# battery5_2.net
KiCad netlist of a schematic drawn in EAGLE
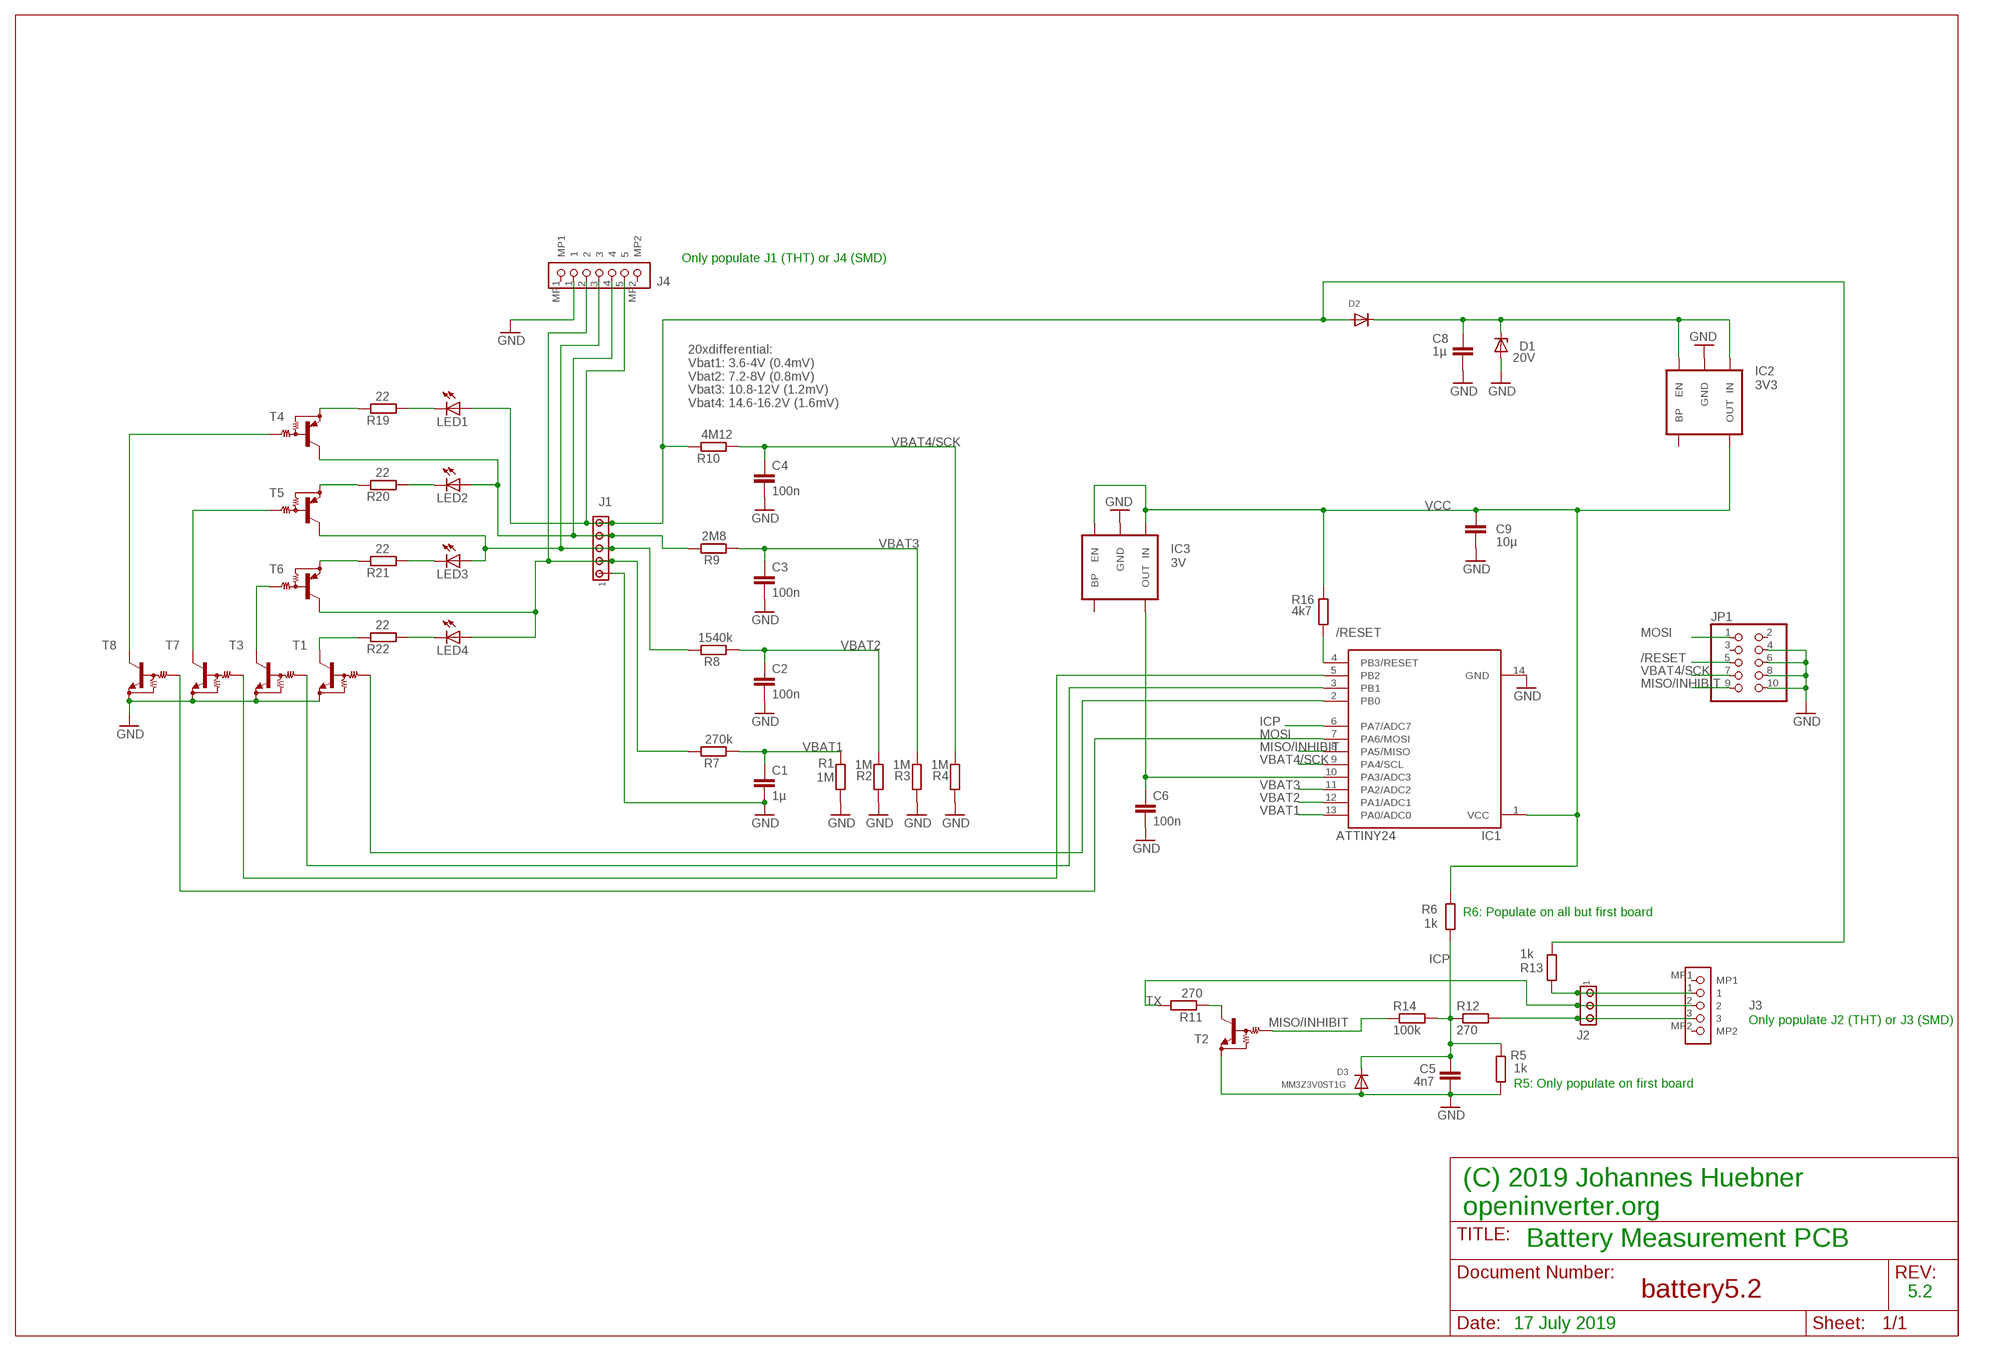
[diagram p0: schematic, sheet 1]

(export (version "E")
  (design (tool "Eeschema 10.0.6"))
  (components
    (comp (ref "C1")
      (value "1µ")
      (footprint "eagle-import:C0603")
      (libsource (lib "eagle-import") (part "C-EUC0603"))
    )
    (comp (ref "C2")
      (value "100n")
      (footprint "eagle-import:C0603")
      (libsource (lib "eagle-import") (part "C-EUC0603"))
    )
    (comp (ref "C3")
      (value "100n")
      (footprint "eagle-import:C0603")
      (libsource (lib "eagle-import") (part "C-EUC0603"))
    )
    (comp (ref "C4")
      (value "100n")
      (footprint "eagle-import:C0603")
      (libsource (lib "eagle-import") (part "C-EUC0603"))
    )
    (comp (ref "C5")
      (value "4n7")
      (footprint "eagle-import:C0603")
      (libsource (lib "eagle-import") (part "C-EUC0603"))
    )
    (comp (ref "C6")
      (value "100n")
      (footprint "eagle-import:C0603")
      (libsource (lib "eagle-import") (part "C-EUC0603"))
    )
    (comp (ref "C8")
      (value "1µ")
      (footprint "eagle-import:C0805")
      (libsource (lib "eagle-import") (part "C-EUC0805"))
    )
    (comp (ref "C9")
      (value "10µ")
      (footprint "eagle-import:C0805")
      (libsource (lib "eagle-import") (part "C-EUC0805"))
    )
    (comp (ref "D1")
      (value "20V")
      (footprint "eagle-import:SMB")
      (libsource (lib "eagle-import") (part "ZENER-DIODESMB"))
    )
    (comp (ref "D2")
      (value "DIODESOD-323F")
      (footprint "eagle-import:SOD-323F")
      (libsource (lib "eagle-import") (part "DIODESOD-323F"))
    )
    (comp (ref "D3")
      (value "MM3Z3V0ST1G")
      (footprint "eagle-import:SOD-323F")
      (libsource (lib "eagle-import") (part "DIODESOD-323F"))
    )
    (comp (ref "IC1")
      (value "ATTINY24")
      (footprint "eagle-import:SO014")
      (libsource (lib "eagle-import") (part "ATTINY24"))
    )
    (comp (ref "IC2")
      (value "3V3")
      (footprint "eagle-import:SOT23-5")
      (libsource (lib "eagle-import") (part "V_REG_LDOSMD"))
    )
    (comp (ref "IC3")
      (value "3V")
      (footprint "eagle-import:SOT23-5")
      (libsource (lib "eagle-import") (part "V_REG_LDOSMD"))
    )
    (comp (ref "J1")
      (value "MTA05-100")
      (footprint "eagle-import:10X05MTA")
      (libsource (lib "eagle-import") (part "MTA05-100"))
    )
    (comp (ref "J2")
      (value "MTA03-100")
      (footprint "eagle-import:10X03MTA")
      (libsource (lib "eagle-import") (part "MTA03-100"))
    )
    (comp (ref "J3")
      (value "BM03B-PASS-1-TFT_(LF)(SN)")
      (footprint "eagle-import:BM03BPASS1TFTLFSN")
      (fields (field (name "MANUFACTURER_PART_NUMBER") "BM03B-PASS-1-TFT (LF)(SN)"))
      (libsource (lib "eagle-import") (part "BM03B-PASS-1-TFT_(LF)(SN)"))
    )
    (comp (ref "J4")
      (value "BM05B-PASS-1-TFT_(LF)(SN)SMD")
      (footprint "eagle-import:BM05BPASS1TFTLFSN")
      (libsource (lib "eagle-import") (part "BM05B-PASS-1-TFT_(LF)(SN)SMD"))
    )
    (comp (ref "JP1")
      (value "PINHD-2X5")
      (footprint "eagle-import:2X05")
      (libsource (lib "eagle-import") (part "PINHD-2X5"))
    )
    (comp (ref "LED1")
      (value "150060GS75000")
      (footprint "eagle-import:CHIPLED_0805")
      (libsource (lib "eagle-import") (part "LEDCHIPLED_0805"))
    )
    (comp (ref "LED2")
      (value "150060GS75000")
      (footprint "eagle-import:CHIPLED_0805")
      (libsource (lib "eagle-import") (part "LEDCHIPLED_0805"))
    )
    (comp (ref "LED3")
      (value "150060GS75000")
      (footprint "eagle-import:CHIPLED_0805")
      (libsource (lib "eagle-import") (part "LEDCHIPLED_0805"))
    )
    (comp (ref "LED4")
      (value "150060GS75000")
      (footprint "eagle-import:CHIPLED_0805")
      (libsource (lib "eagle-import") (part "LEDCHIPLED_0805"))
    )
    (comp (ref "R1")
      (value "1M")
      (footprint "eagle-import:R0603")
      (libsource (lib "eagle-import") (part "R-EU_R0603"))
    )
    (comp (ref "R2")
      (value "1M")
      (footprint "eagle-import:R0603")
      (libsource (lib "eagle-import") (part "R-EU_R0603"))
    )
    (comp (ref "R3")
      (value "1M")
      (footprint "eagle-import:R0603")
      (libsource (lib "eagle-import") (part "R-EU_R0603"))
    )
    (comp (ref "R4")
      (value "1M")
      (footprint "eagle-import:R0603")
      (libsource (lib "eagle-import") (part "R-EU_R0603"))
    )
    (comp (ref "R5")
      (value "1k")
      (footprint "eagle-import:R0603")
      (libsource (lib "eagle-import") (part "R-EU_R0603"))
    )
    (comp (ref "R6")
      (value "1k")
      (footprint "eagle-import:R0603")
      (libsource (lib "eagle-import") (part "R-EU_R0603"))
    )
    (comp (ref "R7")
      (value "270k")
      (footprint "eagle-import:R0603")
      (libsource (lib "eagle-import") (part "R-EU_R0603"))
    )
    (comp (ref "R8")
      (value "1540k")
      (footprint "eagle-import:R0603")
      (libsource (lib "eagle-import") (part "R-EU_R0603"))
    )
    (comp (ref "R9")
      (value "2M8")
      (footprint "eagle-import:R0603")
      (libsource (lib "eagle-import") (part "R-EU_R0603"))
    )
    (comp (ref "R10")
      (value "4M12")
      (footprint "eagle-import:R0603")
      (libsource (lib "eagle-import") (part "R-EU_R0603"))
    )
    (comp (ref "R11")
      (value "270")
      (footprint "eagle-import:R0603")
      (libsource (lib "eagle-import") (part "R-EU_R0603"))
    )
    (comp (ref "R12")
      (value "270")
      (footprint "eagle-import:R0603")
      (libsource (lib "eagle-import") (part "R-EU_R0603"))
    )
    (comp (ref "R13")
      (value "1k")
      (footprint "eagle-import:R0603")
      (libsource (lib "eagle-import") (part "R-EU_R0603"))
    )
    (comp (ref "R14")
      (value "100k")
      (footprint "eagle-import:R0603")
      (libsource (lib "eagle-import") (part "R-EU_R0603"))
    )
    (comp (ref "R16")
      (value "4k7")
      (footprint "eagle-import:R0603")
      (libsource (lib "eagle-import") (part "R-EU_R0603"))
    )
    (comp (ref "R19")
      (value "22")
      (footprint "eagle-import:R0805")
      (libsource (lib "eagle-import") (part "R-EU_R0805"))
    )
    (comp (ref "R20")
      (value "22")
      (footprint "eagle-import:R0805")
      (libsource (lib "eagle-import") (part "R-EU_R0805"))
    )
    (comp (ref "R21")
      (value "22")
      (footprint "eagle-import:R0805")
      (libsource (lib "eagle-import") (part "R-EU_R0805"))
    )
    (comp (ref "R22")
      (value "22")
      (footprint "eagle-import:R0805")
      (libsource (lib "eagle-import") (part "R-EU_R0805"))
    )
    (comp (ref "T1")
      (value "MMUN2233")
      (footprint "eagle-import:SC59-BEC")
      (libsource (lib "eagle-import") (part "-NPN_DRIVER-SC59-BECMUN2211T1"))
    )
    (comp (ref "T2")
      (value "MMUN2233")
      (footprint "eagle-import:SC59-BEC")
      (libsource (lib "eagle-import") (part "-NPN_DRIVER-SC59-BECMUN2211T1"))
    )
    (comp (ref "T3")
      (value "MMUN2233")
      (footprint "eagle-import:SC59-BEC")
      (libsource (lib "eagle-import") (part "-NPN_DRIVER-SC59-BECMUN2211T1"))
    )
    (comp (ref "T4")
      (value "MMUN2111LT1G")
      (footprint "eagle-import:SC59-BEC")
      (libsource (lib "eagle-import") (part "-PNP_DRIVER-SC59-BECMUN2111T1"))
    )
    (comp (ref "T5")
      (value "MMUN2111LT1G")
      (footprint "eagle-import:SC59-BEC")
      (libsource (lib "eagle-import") (part "-PNP_DRIVER-SC59-BECMUN2111T1"))
    )
    (comp (ref "T6")
      (value "MMUN2111LT1G")
      (footprint "eagle-import:SC59-BEC")
      (libsource (lib "eagle-import") (part "-PNP_DRIVER-SC59-BECMUN2111T1"))
    )
    (comp (ref "T7")
      (value "MMUN2233")
      (footprint "eagle-import:SC59-BEC")
      (libsource (lib "eagle-import") (part "-NPN_DRIVER-SC59-BECMUN2211T1"))
    )
    (comp (ref "T8")
      (value "MMUN2233")
      (footprint "eagle-import:SC59-BEC")
      (libsource (lib "eagle-import") (part "-NPN_DRIVER-SC59-BECMUN2211T1"))
    )
  )
  (nets
    (net (code "1") (name "/ICP") (class "Default")
      (node (ref "C5") (pin "1") (pinfunction "1_1") (pintype "passive"))
      (node (ref "D3") (pin "C") (pinfunction "C_C") (pintype "passive"))
      (node (ref "IC1") (pin "6") (pinfunction "PA7/ADC7_6") (pintype "bidirectional"))
      (node (ref "R12") (pin "1") (pinfunction "1_1") (pintype "passive"))
      (node (ref "R14") (pin "2") (pinfunction "2_2") (pintype "passive"))
      (node (ref "R5") (pin "2") (pinfunction "2_2") (pintype "passive"))
      (node (ref "R6") (pin "1") (pinfunction "1_1") (pintype "passive"))
    )
    (net (code "2") (name "/MISO{slash}INHIBIT") (class "Default")
      (node (ref "IC1") (pin "8") (pinfunction "PA5/MISO_8") (pintype "bidirectional"))
      (node (ref "JP1") (pin "9") (pinfunction "9_9") (pintype "passive"))
      (node (ref "R14") (pin "1") (pinfunction "1_1") (pintype "passive"))
      (node (ref "T2") (pin "B") (pinfunction "B_B") (pintype "passive"))
    )
    (net (code "3") (name "/MOSI") (class "Default")
      (node (ref "IC1") (pin "7") (pinfunction "PA6/MOSI_7") (pintype "bidirectional"))
      (node (ref "JP1") (pin "1") (pinfunction "1_1") (pintype "passive"))
      (node (ref "T8") (pin "B") (pinfunction "B_B") (pintype "passive"))
    )
    (net (code "4") (name "/TX") (class "Default")
      (node (ref "J2") (pin "2") (pinfunction "2_2") (pintype "passive"))
      (node (ref "J3") (pin "2") (pinfunction "2_2") (pintype "bidirectional"))
      (node (ref "R11") (pin "2") (pinfunction "2_2") (pintype "passive"))
    )
    (net (code "5") (name "/VBAT1") (class "Default")
      (node (ref "C1") (pin "1") (pinfunction "1_1") (pintype "passive"))
      (node (ref "IC1") (pin "13") (pinfunction "PA0/ADC0_13") (pintype "bidirectional"))
      (node (ref "R1") (pin "1") (pinfunction "1_1") (pintype "passive"))
      (node (ref "R7") (pin "1") (pinfunction "1_1") (pintype "passive"))
    )
    (net (code "6") (name "/VBAT2") (class "Default")
      (node (ref "C2") (pin "1") (pinfunction "1_1") (pintype "passive"))
      (node (ref "IC1") (pin "12") (pinfunction "PA1/ADC1_12") (pintype "bidirectional"))
      (node (ref "R2") (pin "1") (pinfunction "1_1") (pintype "passive"))
      (node (ref "R8") (pin "1") (pinfunction "1_1") (pintype "passive"))
    )
    (net (code "7") (name "/VBAT3") (class "Default")
      (node (ref "C3") (pin "1") (pinfunction "1_1") (pintype "passive"))
      (node (ref "IC1") (pin "11") (pinfunction "PA2/ADC2_11") (pintype "bidirectional"))
      (node (ref "R3") (pin "1") (pinfunction "1_1") (pintype "passive"))
      (node (ref "R9") (pin "1") (pinfunction "1_1") (pintype "passive"))
    )
    (net (code "8") (name "/VBAT4{slash}SCK") (class "Default")
      (node (ref "C4") (pin "1") (pinfunction "1_1") (pintype "passive"))
      (node (ref "IC1") (pin "9") (pinfunction "PA4/SCL_9") (pintype "bidirectional"))
      (node (ref "JP1") (pin "7") (pinfunction "7_7") (pintype "passive"))
      (node (ref "R10") (pin "1") (pinfunction "1_1") (pintype "passive"))
      (node (ref "R4") (pin "1") (pinfunction "1_1") (pintype "passive"))
    )
    (net (code "9") (name "/VCC") (class "Default")
      (node (ref "C9") (pin "1") (pinfunction "1_1") (pintype "passive"))
      (node (ref "IC1") (pin "1") (pinfunction "VCC_1") (pintype "bidirectional"))
      (node (ref "IC2") (pin "5") (pinfunction "OUT_5") (pintype "passive"))
      (node (ref "IC3") (pin "1") (pinfunction "IN_1") (pintype "input"))
      (node (ref "IC3") (pin "3") (pinfunction "EN_3") (pintype "input"))
      (node (ref "R16") (pin "1") (pinfunction "1_1") (pintype "passive"))
      (node (ref "R6") (pin "2") (pinfunction "2_2") (pintype "passive"))
    )
    (net (code "10") (name "/{slash}RESET") (class "Default")
      (node (ref "IC1") (pin "4") (pinfunction "PB3/RESET_4") (pintype "bidirectional"))
      (node (ref "JP1") (pin "5") (pinfunction "5_5") (pintype "passive"))
      (node (ref "R16") (pin "2") (pinfunction "2_2") (pintype "passive"))
    )
    (net (code "11") (name "GND") (class "Default")
      (node (ref "C1") (pin "2") (pinfunction "2_2") (pintype "passive"))
      (node (ref "C2") (pin "2") (pinfunction "2_2") (pintype "passive"))
      (node (ref "C3") (pin "2") (pinfunction "2_2") (pintype "passive"))
      (node (ref "C4") (pin "2") (pinfunction "2_2") (pintype "passive"))
      (node (ref "C5") (pin "2") (pinfunction "2_2") (pintype "passive"))
      (node (ref "C6") (pin "2") (pinfunction "2_2") (pintype "passive"))
      (node (ref "C8") (pin "2") (pinfunction "2_2") (pintype "passive"))
      (node (ref "C9") (pin "2") (pinfunction "2_2") (pintype "passive"))
      (node (ref "D1") (pin "A") (pinfunction "A_A") (pintype "passive"))
      (node (ref "D3") (pin "A") (pinfunction "A_A") (pintype "passive"))
      (node (ref "IC1") (pin "14") (pinfunction "GND_14") (pintype "bidirectional"))
      (node (ref "IC2") (pin "2") (pinfunction "GND_2") (pintype "input"))
      (node (ref "IC3") (pin "2") (pinfunction "GND_2") (pintype "input"))
      (node (ref "J1") (pin "1") (pinfunction "1_1") (pintype "passive"))
      (node (ref "J4") (pin "1") (pinfunction "1_1") (pintype "bidirectional"))
      (node (ref "JP1") (pin "10") (pinfunction "10_10") (pintype "passive"))
      (node (ref "JP1") (pin "4") (pinfunction "4_4") (pintype "passive"))
      (node (ref "JP1") (pin "6") (pinfunction "6_6") (pintype "passive"))
      (node (ref "JP1") (pin "8") (pinfunction "8_8") (pintype "passive"))
      (node (ref "R1") (pin "2") (pinfunction "2_2") (pintype "passive"))
      (node (ref "R2") (pin "2") (pinfunction "2_2") (pintype "passive"))
      (node (ref "R3") (pin "2") (pinfunction "2_2") (pintype "passive"))
      (node (ref "R4") (pin "2") (pinfunction "2_2") (pintype "passive"))
      (node (ref "R5") (pin "1") (pinfunction "1_1") (pintype "passive"))
      (node (ref "T1") (pin "E") (pinfunction "E_E") (pintype "passive"))
      (node (ref "T2") (pin "E") (pinfunction "E_E") (pintype "passive"))
      (node (ref "T3") (pin "E") (pinfunction "E_E") (pintype "passive"))
      (node (ref "T7") (pin "E") (pinfunction "E_E") (pintype "passive"))
      (node (ref "T8") (pin "E") (pinfunction "E_E") (pintype "passive"))
    )
    (net (code "12") (name "Net-(D2-PadA)") (class "Default")
      (node (ref "D2") (pin "A") (pinfunction "A_A") (pintype "passive"))
      (node (ref "J1") (pin "5") (pinfunction "5_5") (pintype "passive"))
      (node (ref "J4") (pin "5") (pinfunction "5_5") (pintype "bidirectional"))
      (node (ref "LED1") (pin "A") (pinfunction "A_A") (pintype "passive"))
      (node (ref "R10") (pin "2") (pinfunction "2_2") (pintype "passive"))
      (node (ref "R13") (pin "1") (pinfunction "1_1") (pintype "passive"))
    )
    (net (code "13") (name "Net-(IC1-PA3{slash}ADC3)") (class "Default")
      (node (ref "C6") (pin "1") (pinfunction "1_1") (pintype "passive"))
      (node (ref "IC1") (pin "10") (pinfunction "PA3/ADC3_10") (pintype "bidirectional"))
      (node (ref "IC3") (pin "5") (pinfunction "OUT_5") (pintype "passive"))
    )
    (net (code "14") (name "Net-(IC1-PB0)") (class "Default")
      (node (ref "IC1") (pin "2") (pinfunction "PB0_2") (pintype "bidirectional"))
      (node (ref "T1") (pin "B") (pinfunction "B_B") (pintype "passive"))
    )
    (net (code "15") (name "Net-(IC1-PB1)") (class "Default")
      (node (ref "IC1") (pin "3") (pinfunction "PB1_3") (pintype "bidirectional"))
      (node (ref "T3") (pin "B") (pinfunction "B_B") (pintype "passive"))
    )
    (net (code "16") (name "Net-(IC1-PB2)") (class "Default")
      (node (ref "IC1") (pin "5") (pinfunction "PB2_5") (pintype "bidirectional"))
      (node (ref "T7") (pin "B") (pinfunction "B_B") (pintype "passive"))
    )
    (net (code "17") (name "Net-(IC2-EN)") (class "Default")
      (node (ref "C8") (pin "1") (pinfunction "1_1") (pintype "passive"))
      (node (ref "D1") (pin "C") (pinfunction "C_C") (pintype "passive"))
      (node (ref "D2") (pin "C") (pinfunction "C_C") (pintype "passive"))
      (node (ref "IC2") (pin "1") (pinfunction "IN_1") (pintype "input"))
      (node (ref "IC2") (pin "3") (pinfunction "EN_3") (pintype "input"))
    )
    (net (code "18") (name "Net-(J1-Pad2)") (class "Default")
      (node (ref "J1") (pin "2") (pinfunction "2_2") (pintype "passive"))
      (node (ref "J4") (pin "2") (pinfunction "2_2") (pintype "bidirectional"))
      (node (ref "LED4") (pin "A") (pinfunction "A_A") (pintype "passive"))
      (node (ref "R7") (pin "2") (pinfunction "2_2") (pintype "passive"))
      (node (ref "T6") (pin "C") (pinfunction "C_C") (pintype "passive"))
    )
    (net (code "19") (name "Net-(J1-Pad3)") (class "Default")
      (node (ref "J1") (pin "3") (pinfunction "3_3") (pintype "passive"))
      (node (ref "J4") (pin "3") (pinfunction "3_3") (pintype "bidirectional"))
      (node (ref "LED3") (pin "A") (pinfunction "A_A") (pintype "passive"))
      (node (ref "R8") (pin "2") (pinfunction "2_2") (pintype "passive"))
      (node (ref "T5") (pin "C") (pinfunction "C_C") (pintype "passive"))
    )
    (net (code "20") (name "Net-(J1-Pad4)") (class "Default")
      (node (ref "J1") (pin "4") (pinfunction "4_4") (pintype "passive"))
      (node (ref "J4") (pin "4") (pinfunction "4_4") (pintype "bidirectional"))
      (node (ref "LED2") (pin "A") (pinfunction "A_A") (pintype "passive"))
      (node (ref "R9") (pin "2") (pinfunction "2_2") (pintype "passive"))
      (node (ref "T4") (pin "C") (pinfunction "C_C") (pintype "passive"))
    )
    (net (code "21") (name "Net-(J2-Pad1)") (class "Default")
      (node (ref "J2") (pin "1") (pinfunction "1_1") (pintype "passive"))
      (node (ref "J3") (pin "1") (pinfunction "1_1") (pintype "bidirectional"))
      (node (ref "R13") (pin "2") (pinfunction "2_2") (pintype "passive"))
    )
    (net (code "22") (name "Net-(J2-Pad3)") (class "Default")
      (node (ref "J2") (pin "3") (pinfunction "3_3") (pintype "passive"))
      (node (ref "J3") (pin "3") (pinfunction "3_3") (pintype "bidirectional"))
      (node (ref "R12") (pin "2") (pinfunction "2_2") (pintype "passive"))
    )
    (net (code "23") (name "Net-(LED1-PadC)") (class "Default")
      (node (ref "LED1") (pin "C") (pinfunction "C_C") (pintype "passive"))
      (node (ref "R19") (pin "1") (pinfunction "1_1") (pintype "passive"))
    )
    (net (code "24") (name "Net-(LED2-PadC)") (class "Default")
      (node (ref "LED2") (pin "C") (pinfunction "C_C") (pintype "passive"))
      (node (ref "R20") (pin "1") (pinfunction "1_1") (pintype "passive"))
    )
    (net (code "25") (name "Net-(LED3-PadC)") (class "Default")
      (node (ref "LED3") (pin "C") (pinfunction "C_C") (pintype "passive"))
      (node (ref "R21") (pin "1") (pinfunction "1_1") (pintype "passive"))
    )
    (net (code "26") (name "Net-(LED4-PadC)") (class "Default")
      (node (ref "LED4") (pin "C") (pinfunction "C_C") (pintype "passive"))
      (node (ref "R22") (pin "1") (pinfunction "1_1") (pintype "passive"))
    )
    (net (code "27") (name "Net-(R11-Pad1)") (class "Default")
      (node (ref "R11") (pin "1") (pinfunction "1_1") (pintype "passive"))
      (node (ref "T2") (pin "C") (pinfunction "C_C") (pintype "passive"))
    )
    (net (code "28") (name "Net-(R19-Pad2)") (class "Default")
      (node (ref "R19") (pin "2") (pinfunction "2_2") (pintype "passive"))
      (node (ref "T4") (pin "E") (pinfunction "E_E") (pintype "passive"))
    )
    (net (code "29") (name "Net-(R20-Pad2)") (class "Default")
      (node (ref "R20") (pin "2") (pinfunction "2_2") (pintype "passive"))
      (node (ref "T5") (pin "E") (pinfunction "E_E") (pintype "passive"))
    )
    (net (code "30") (name "Net-(R21-Pad2)") (class "Default")
      (node (ref "R21") (pin "2") (pinfunction "2_2") (pintype "passive"))
      (node (ref "T6") (pin "E") (pinfunction "E_E") (pintype "passive"))
    )
    (net (code "31") (name "Net-(R22-Pad2)") (class "Default")
      (node (ref "R22") (pin "2") (pinfunction "2_2") (pintype "passive"))
      (node (ref "T1") (pin "C") (pinfunction "C_C") (pintype "passive"))
    )
    (net (code "32") (name "Net-(T3-PadC)") (class "Default")
      (node (ref "T3") (pin "C") (pinfunction "C_C") (pintype "passive"))
      (node (ref "T6") (pin "B") (pinfunction "B_B") (pintype "passive"))
    )
    (net (code "33") (name "Net-(T4-PadB)") (class "Default")
      (node (ref "T4") (pin "B") (pinfunction "B_B") (pintype "passive"))
      (node (ref "T8") (pin "C") (pinfunction "C_C") (pintype "passive"))
    )
    (net (code "34") (name "Net-(T5-PadB)") (class "Default")
      (node (ref "T5") (pin "B") (pinfunction "B_B") (pintype "passive"))
      (node (ref "T7") (pin "C") (pinfunction "C_C") (pintype "passive"))
    )
    (net (code "35") (name "unconnected-(IC2-BP-Pad4)") (class "Default")
      (node (ref "IC2") (pin "4") (pinfunction "BP_4") (pintype "input"))
    )
    (net (code "36") (name "unconnected-(IC3-BP-Pad4)") (class "Default")
      (node (ref "IC3") (pin "4") (pinfunction "BP_4") (pintype "input"))
    )
    (net (code "37") (name "unconnected-(J3-PadMP1)") (class "Default")
      (node (ref "J3") (pin "MP1") (pinfunction "MP1_MP1") (pintype "bidirectional"))
    )
    (net (code "38") (name "unconnected-(J3-PadMP2)") (class "Default")
      (node (ref "J3") (pin "MP2") (pinfunction "MP2_MP2") (pintype "bidirectional"))
    )
    (net (code "39") (name "unconnected-(J4-PadMP1)") (class "Default")
      (node (ref "J4") (pin "MP1") (pinfunction "MP1_MP1") (pintype "bidirectional"))
    )
    (net (code "40") (name "unconnected-(J4-PadMP2)") (class "Default")
      (node (ref "J4") (pin "MP2") (pinfunction "MP2_MP2") (pintype "bidirectional"))
    )
    (net (code "41") (name "unconnected-(JP1-Pad2)") (class "Default")
      (node (ref "JP1") (pin "2") (pinfunction "2_2") (pintype "passive"))
    )
    (net (code "42") (name "unconnected-(JP1-Pad3)") (class "Default")
      (node (ref "JP1") (pin "3") (pinfunction "3_3") (pintype "passive"))
    )
  )
)
